# blinky.net
KiCad netlist of a schematic drawn in EAGLE
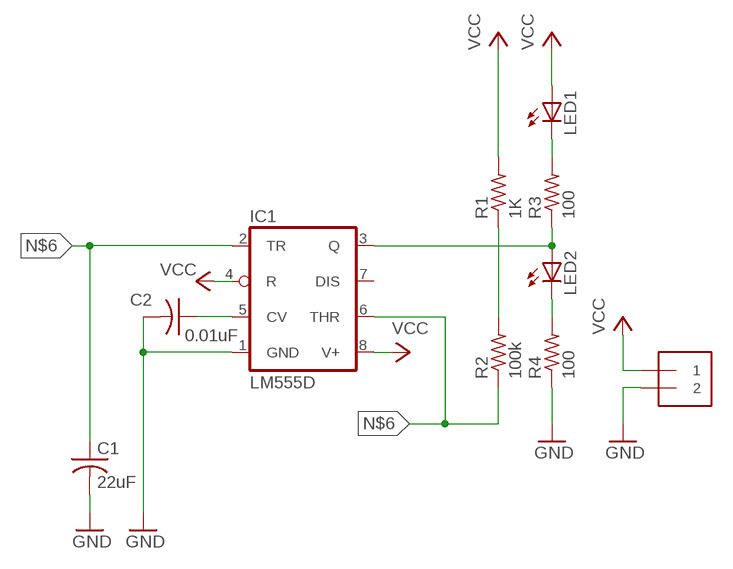
[diagram p0: schematic, sheet 1]

(export (version "E")
  (design (tool "Eeschema 10.0.6"))
  (components
    (comp (ref "C1")
      (value "22uF")
      (footprint "eagle-import:C0805")
      (libsource (lib "eagle-import") (part "C-USC0805"))
    )
    (comp (ref "C2")
      (value "0.01uF")
      (footprint "eagle-import:C0805")
      (libsource (lib "eagle-import") (part "C-USC0805"))
    )
    (comp (ref "IC1")
      (value "LM555D")
      (footprint "eagle-import:SO08")
      (libsource (lib "eagle-import") (part "555DLM"))
    )
    (comp (ref "J1")
      (value "1X2-3.5MM")
      (footprint "eagle-import:1X2-3.5MM")
      (libsource (lib "eagle-import") (part "1X2-3.5MM"))
    )
    (comp (ref "LED1")
      (value "LEDCHIPLED_0805")
      (footprint "eagle-import:CHIPLED_0805")
      (libsource (lib "eagle-import") (part "LEDCHIPLED_0805"))
    )
    (comp (ref "LED2")
      (value "LEDCHIPLED_0805")
      (footprint "eagle-import:CHIPLED_0805")
      (libsource (lib "eagle-import") (part "LEDCHIPLED_0805"))
    )
    (comp (ref "R1")
      (value "1K")
      (footprint "eagle-import:R0805")
      (libsource (lib "eagle-import") (part "R-US_R0805"))
    )
    (comp (ref "R2")
      (value "100k")
      (footprint "eagle-import:R0805")
      (libsource (lib "eagle-import") (part "R-US_R0805"))
    )
    (comp (ref "R3")
      (value "100")
      (footprint "eagle-import:R0805")
      (libsource (lib "eagle-import") (part "R-US_R0805"))
    )
    (comp (ref "R4")
      (value "100")
      (footprint "eagle-import:R0805")
      (libsource (lib "eagle-import") (part "R-US_R0805"))
    )
  )
  (nets
    (net (code "1") (name "GND") (class "Default")
      (node (ref "C1") (pin "2") (pinfunction "2_2") (pintype "passive"))
      (node (ref "C2") (pin "2") (pinfunction "2_2") (pintype "passive"))
      (node (ref "IC1") (pin "1") (pinfunction "GND_1") (pintype "power_in"))
      (node (ref "J1") (pin "2") (pinfunction "2_2") (pintype "passive"))
      (node (ref "R4") (pin "1") (pinfunction "1_1") (pintype "passive"))
    )
    (net (code "2") (name "N$6") (class "Default")
      (node (ref "C1") (pin "1") (pinfunction "1_1") (pintype "passive"))
      (node (ref "IC1") (pin "2") (pinfunction "TR_2") (pintype "input"))
      (node (ref "IC1") (pin "6") (pinfunction "THR_6") (pintype "input"))
      (node (ref "R2") (pin "1") (pinfunction "1_1") (pintype "passive"))
    )
    (net (code "3") (name "Net-(IC1-CV)") (class "Default")
      (node (ref "C2") (pin "1") (pinfunction "1_1") (pintype "passive"))
      (node (ref "IC1") (pin "5") (pinfunction "CV_5") (pintype "input"))
    )
    (net (code "4") (name "Net-(IC1-Q)") (class "Default")
      (node (ref "IC1") (pin "3") (pinfunction "Q_3") (pintype "output"))
      (node (ref "LED2") (pin "A") (pinfunction "A_A") (pintype "passive"))
      (node (ref "R3") (pin "1") (pinfunction "1_1") (pintype "passive"))
    )
    (net (code "5") (name "Net-(LED1-PadC)") (class "Default")
      (node (ref "LED1") (pin "C") (pinfunction "C_C") (pintype "passive"))
      (node (ref "R3") (pin "2") (pinfunction "2_2") (pintype "passive"))
    )
    (net (code "6") (name "Net-(LED2-PadC)") (class "Default")
      (node (ref "LED2") (pin "C") (pinfunction "C_C") (pintype "passive"))
      (node (ref "R4") (pin "2") (pinfunction "2_2") (pintype "passive"))
    )
    (net (code "7") (name "Net-(R1-Pad1)") (class "Default")
      (node (ref "R1") (pin "1") (pinfunction "1_1") (pintype "passive"))
      (node (ref "R2") (pin "2") (pinfunction "2_2") (pintype "passive"))
    )
    (net (code "8") (name "VCC") (class "Default")
      (node (ref "IC1") (pin "4") (pinfunction "R_4") (pintype "input"))
      (node (ref "IC1") (pin "8") (pinfunction "V+_8") (pintype "power_in"))
      (node (ref "J1") (pin "1") (pinfunction "1_1") (pintype "passive"))
      (node (ref "LED1") (pin "A") (pinfunction "A_A") (pintype "passive"))
      (node (ref "R1") (pin "2") (pinfunction "2_2") (pintype "passive"))
    )
    (net (code "9") (name "unconnected-(IC1-DIS-Pad7)") (class "Default")
      (node (ref "IC1") (pin "7") (pinfunction "DIS_7") (pintype "input"))
    )
  )
)
